# Load_Cell_Amp.net
KiCad netlist of a schematic drawn in Altium Designer
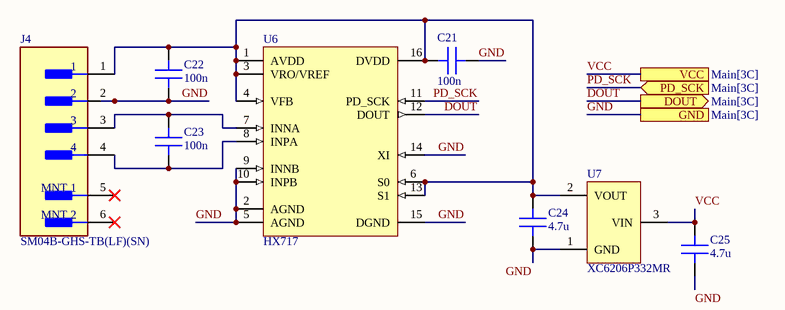
[diagram p0: Load Cell Amp.SchDoc]

(export (version "E")
  (design (tool "Eeschema 10.0.6"))
  (components
    (comp (ref "C21")
      (value "100n")
      (footprint "IPC C C0402 NO SILK")
      (libsource (lib "JLCPCB Library") (part "Generic CAP 0402"))
    )
    (comp (ref "C22")
      (value "100n")
      (footprint "IPC C C0402 NO SILK")
      (libsource (lib "JLCPCB Library") (part "Generic CAP 0402"))
    )
    (comp (ref "C23")
      (value "100n")
      (footprint "IPC C C0402 NO SILK")
      (libsource (lib "JLCPCB Library") (part "Generic CAP 0402"))
    )
    (comp (ref "C24")
      (value "4.7u")
      (footprint "IPC C C0603 NO SILK")
      (libsource (lib "JLCPCB Library") (part "Generic CAP 0603"))
    )
    (comp (ref "C25")
      (value "4.7u")
      (footprint "IPC C C0603 NO SILK")
      (libsource (lib "JLCPCB Library") (part "Generic CAP 0603"))
    )
    (comp (ref "J4")
      (value "SM04B-GHS-TB(LF)(SN)")
      (footprint "FP-SM04B-GHS-TB_LF_SN-MFG")
      (description "CONN HEADER SMD R/A 4POS 1.25MM")
      (libsource (lib "Altium Content Vault") (part "f4320a1371cd6270e33bce1916c33c0"))
    )
    (comp (ref "U6")
      (value "HX717")
      (footprint "SOIC127P600X160-16L")
      (libsource (lib "Schlib1") (part "HX717"))
    )
    (comp (ref "U7")
      (value "XC6206P332MR")
      (footprint "SOT23-3")
      (fields (field (name "MANUFACTURER") "TOREX(特瑞仕)"))
      (libsource (lib "JLCPCB Library") (part "3.3V Regulator XC6206P332MR_C5446"))
    )
  )
  (nets
    (net (code "1") (name "/DOUT") (class "Default")
      (node (ref "U6") (pin "12") (pinfunction "DOUT_12") (pintype "output"))
    )
    (net (code "2") (name "/GND") (class "Default")
      (node (ref "C21") (pin "1") (pinfunction "1_1") (pintype "passive"))
      (node (ref "C22") (pin "1") (pinfunction "1_1") (pintype "passive"))
      (node (ref "C24") (pin "1") (pinfunction "1_1") (pintype "passive"))
      (node (ref "C25") (pin "1") (pinfunction "1_1") (pintype "passive"))
      (node (ref "J4") (pin "2") (pinfunction "2_2") (pintype "passive"))
      (node (ref "U6") (pin "10") (pinfunction "INPB_10") (pintype "input"))
      (node (ref "U6") (pin "14") (pinfunction "XI_14") (pintype "input"))
      (node (ref "U6") (pin "15") (pinfunction "DGND_15") (pintype "power_in"))
      (node (ref "U6") (pin "2") (pinfunction "AGND_2") (pintype "power_in"))
      (node (ref "U6") (pin "5") (pinfunction "AGND_5") (pintype "power_in"))
      (node (ref "U6") (pin "9") (pinfunction "INNB_9") (pintype "input"))
      (node (ref "U7") (pin "1") (pinfunction "GND_1") (pintype "power_in"))
    )
    (net (code "3") (name "/PD_SCK") (class "Default")
      (node (ref "U6") (pin "11") (pinfunction "PD_SCK_11") (pintype "input"))
    )
    (net (code "4") (name "/VCC") (class "Default")
      (node (ref "C25") (pin "2") (pinfunction "2_2") (pintype "passive"))
      (node (ref "U7") (pin "3") (pinfunction "VIN_3") (pintype "power_in"))
    )
    (net (code "5") (name "Net-(U6-AVDD)") (class "Default")
      (node (ref "C21") (pin "2") (pinfunction "2_2") (pintype "passive"))
      (node (ref "C22") (pin "2") (pinfunction "2_2") (pintype "passive"))
      (node (ref "C24") (pin "2") (pinfunction "2_2") (pintype "passive"))
      (node (ref "J4") (pin "1") (pinfunction "1_1") (pintype "passive"))
      (node (ref "U6") (pin "1") (pinfunction "AVDD_1") (pintype "power_in"))
      (node (ref "U6") (pin "13") (pinfunction "S1_13") (pintype "input"))
      (node (ref "U6") (pin "16") (pinfunction "DVDD_16") (pintype "power_in"))
      (node (ref "U6") (pin "3") (pinfunction "VRO/VREF_3") (pintype "passive"))
      (node (ref "U6") (pin "4") (pinfunction "VFB_4") (pintype "input"))
      (node (ref "U6") (pin "6") (pinfunction "S0_6") (pintype "input"))
      (node (ref "U7") (pin "2") (pinfunction "VOUT_2") (pintype "power_in"))
    )
    (net (code "6") (name "Net-(U6-INNA)") (class "Default")
      (node (ref "C23") (pin "2") (pinfunction "2_2") (pintype "passive"))
      (node (ref "J4") (pin "3") (pinfunction "3_3") (pintype "passive"))
      (node (ref "U6") (pin "7") (pinfunction "INNA_7") (pintype "input"))
    )
    (net (code "7") (name "Net-(U6-INPA)") (class "Default")
      (node (ref "C23") (pin "1") (pinfunction "1_1") (pintype "passive"))
      (node (ref "J4") (pin "4") (pinfunction "4_4") (pintype "passive"))
      (node (ref "U6") (pin "8") (pinfunction "INPA_8") (pintype "input"))
    )
    (net (code "8") (name "unconnected-(J4-MNT_1-Pad5)") (class "Default")
      (node (ref "J4") (pin "5") (pinfunction "MNT_1_5") (pintype "passive+no_connect"))
    )
    (net (code "9") (name "unconnected-(J4-MNT_2-Pad6)") (class "Default")
      (node (ref "J4") (pin "6") (pinfunction "MNT_2_6") (pintype "passive+no_connect"))
    )
  )
)
